# Schematic-ver1.net
KiCad netlist of a schematic drawn in Altium Designer
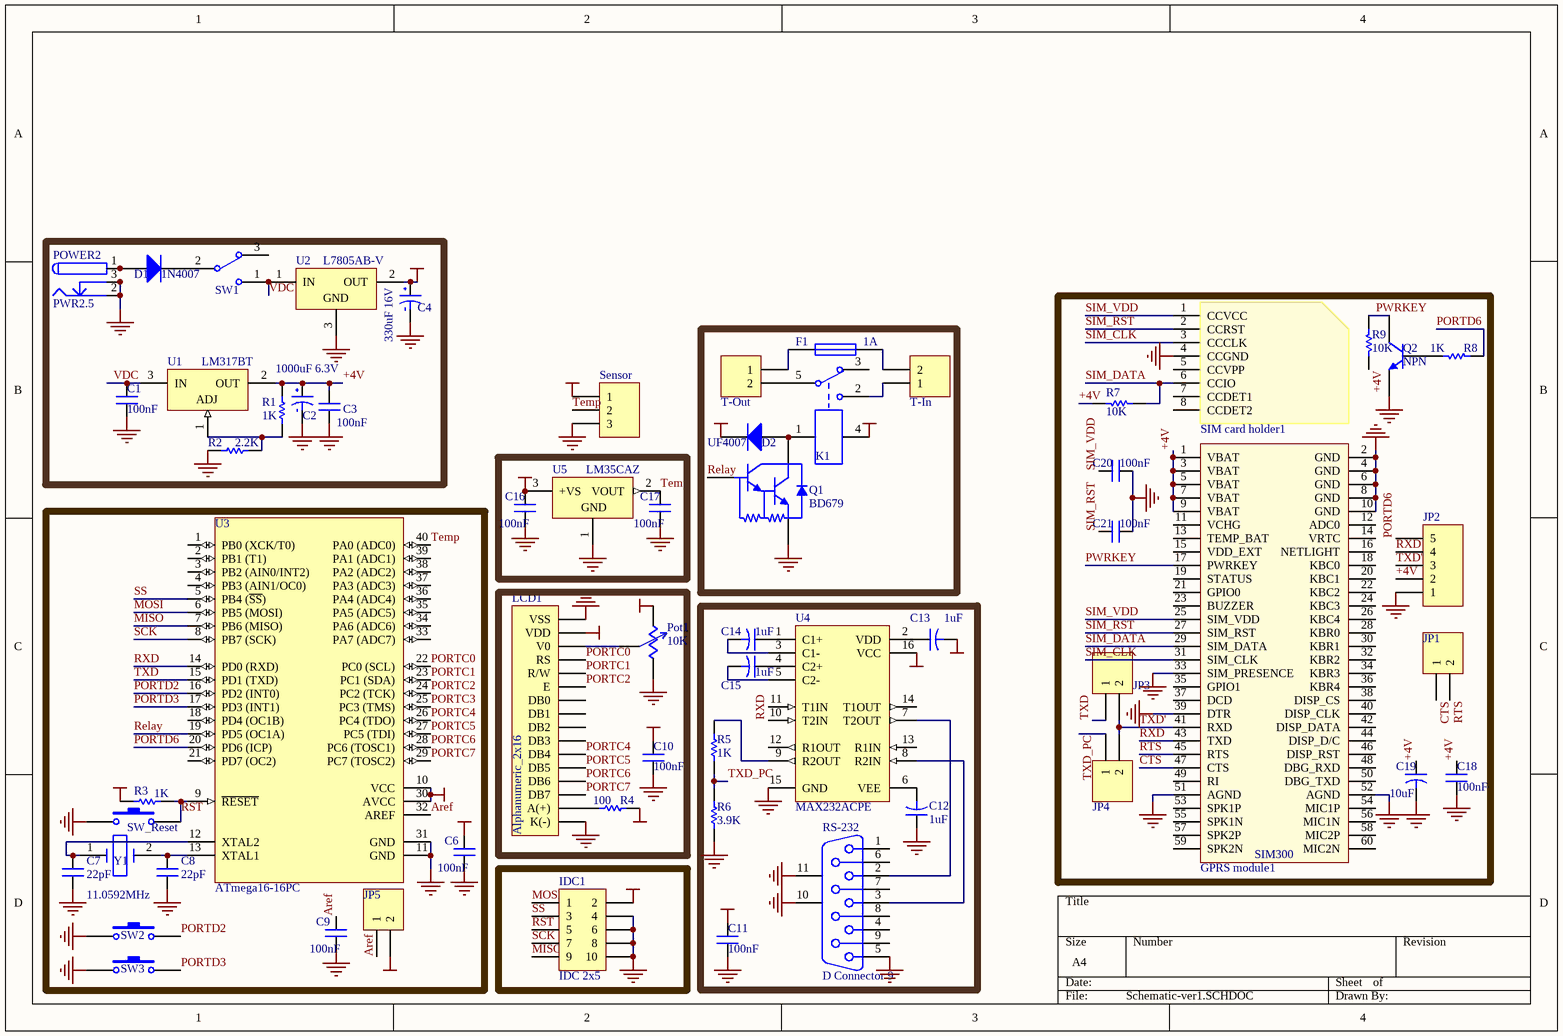
[diagram p0: Schematic-ver1.SCHDOC]

(export (version "E")
  (design (tool "Eeschema 10.0.6"))
  (components
    (comp (ref "C1")
      (value "Cap_Ceramic")
      (footprint "Cap_Ceramic")
      (fields (field (name "ALTIUM_UNNAMED_1") "100nF"))
      (libsource (lib "MMTcomponnents") (part "Cap_Ceramic"))
    )
    (comp (ref "C2")
      (value "Cap_5mm")
      (footprint "Cap_5mm")
      (fields (field (name "ALTIUM_UNNAMED_1") "1000uF 6.3V"))
      (libsource (lib "MMTcomponnents") (part "Cap_5mm"))
    )
    (comp (ref "C3")
      (value "Cap_Ceramic")
      (footprint "Cap_Ceramic")
      (fields (field (name "ALTIUM_UNNAMED_1") "100nF"))
      (libsource (lib "MMTcomponnents") (part "Cap_Ceramic"))
    )
    (comp (ref "C4")
      (value "Cap_4mm")
      (footprint "Cap_4mm")
      (fields (field (name "ALTIUM_UNNAMED_1") "330uF 16V"))
      (libsource (lib "MMTcomponnents") (part "Cap_4mm"))
    )
    (comp (ref "C6")
      (value "Cap_Tantalium")
      (footprint "Cap_Ceramic")
      (fields (field (name "ALTIUM_UNNAMED_1") "100nF"))
      (libsource (lib "MMTcomponnents") (part "Cap_Ceramic"))
    )
    (comp (ref "C7")
      (value "Cap_Ceramic")
      (footprint "Cap_Ceramic")
      (fields (field (name "ALTIUM_UNNAMED_1") "22pF"))
      (libsource (lib "MMTcomponnents") (part "Cap_Ceramic"))
    )
    (comp (ref "C8")
      (value "Cap_Ceramic")
      (footprint "Cap_Ceramic")
      (fields (field (name "ALTIUM_UNNAMED_1") "22pF"))
      (libsource (lib "MMTcomponnents") (part "Cap_Ceramic"))
    )
    (comp (ref "C9")
      (value "Cap_Tantalium")
      (footprint "Cap_Ceramic")
      (fields (field (name "ALTIUM_UNNAMED_1") "100nF"))
      (libsource (lib "MMTcomponnents") (part "Cap_Ceramic"))
    )
    (comp (ref "C10")
      (value "Cap_Tantalium")
      (footprint "Cap_Ceramic")
      (fields (field (name "ALTIUM_UNNAMED_1") "100nF"))
      (libsource (lib "MMTcomponnents") (part "Cap_Ceramic"))
    )
    (comp (ref "C11")
      (value "Cap_Tantalium")
      (footprint "Cap_Ceramic")
      (fields (field (name "ALTIUM_UNNAMED_1") "100nF"))
      (libsource (lib "MMTcomponnents") (part "Cap_Ceramic"))
    )
    (comp (ref "C12")
      (value "Cap_Small")
      (footprint "Cap_Small")
      (fields (field (name "ALTIUM_UNNAMED_1") "1uF"))
      (libsource (lib "MMTcomponnents") (part "Cap_Small"))
    )
    (comp (ref "C13")
      (value "Cap_Small")
      (footprint "Cap_Small")
      (fields (field (name "ALTIUM_UNNAMED_1") "1uF"))
      (libsource (lib "MMTcomponnents") (part "Cap_Small"))
    )
    (comp (ref "C14")
      (value "Cap_Small")
      (footprint "Cap_Small")
      (fields (field (name "ALTIUM_UNNAMED_1") "1uF"))
      (libsource (lib "MMTcomponnents") (part "Cap_Small"))
    )
    (comp (ref "C15")
      (value "Cap_Small")
      (footprint "Cap_Small")
      (fields (field (name "ALTIUM_UNNAMED_1") "1uF"))
      (libsource (lib "MMTcomponnents") (part "Cap_Small"))
    )
    (comp (ref "C16")
      (value "Cap_Tantalium")
      (footprint "Cap_Ceramic")
      (fields (field (name "ALTIUM_UNNAMED_1") "100nF"))
      (libsource (lib "MMTcomponnents") (part "Cap_Ceramic"))
    )
    (comp (ref "C17")
      (value "Cap_Tantalium")
      (footprint "Cap_Ceramic")
      (fields (field (name "ALTIUM_UNNAMED_1") "100nF"))
      (libsource (lib "MMTcomponnents") (part "Cap_Ceramic"))
    )
    (comp (ref "C18")
      (value "Cap_Tantalium")
      (footprint "Cap_Ceramic")
      (fields (field (name "ALTIUM_UNNAMED_1") "100nF"))
      (libsource (lib "MMTcomponnents") (part "Cap_Ceramic"))
    )
    (comp (ref "C19")
      (value "Cap_Small")
      (footprint "Cap_Small")
      (fields (field (name "ALTIUM_UNNAMED_1") "10uF"))
      (libsource (lib "MMTcomponnents") (part "Cap_Small"))
    )
    (comp (ref "C20")
      (value "Cap_Tantalium")
      (footprint "Cap_Ceramic")
      (fields (field (name "ALTIUM_UNNAMED_1") "100nF"))
      (libsource (lib "MMTcomponnents") (part "Cap_Ceramic"))
    )
    (comp (ref "C21")
      (value "Cap_Tantalium")
      (footprint "Cap_Ceramic")
      (fields (field (name "ALTIUM_UNNAMED_1") "100nF"))
      (libsource (lib "MMTcomponnents") (part "Cap_Ceramic"))
    )
    (comp (ref "D1")
      (value "1N4007")
      (footprint "Diode 1N4001")
      (libsource (lib "MMTcomponnents") (part "Diode 1N4001"))
    )
    (comp (ref "D2")
      (value "UF4007")
      (footprint "Diode 1N4001")
      (libsource (lib "MMTcomponnents") (part "Diode 1N4001"))
    )
    (comp (ref "F1")
      (value "Fuse2")
      (footprint "Fuse2")
      (fields (field (name "ALTIUM_UNNAMED_1") "1A"))
      (libsource (lib "MMTcomponnents") (part "Fuse2"))
    )
    (comp (ref "GPRS module1")
      (value "SIM300")
      (footprint "SIM300")
      (libsource (lib "MMTcomponnents") (part "SIM300"))
    )
    (comp (ref "IDC1")
      (value "IDC 2x5")
      (footprint "IDC 2x5")
      (libsource (lib "MMTcomponnents") (part "IDC 2x5"))
    )
    (comp (ref "JP1")
      (value "Header 2")
      (footprint "HDR1X2")
      (description "Header, 2-Pin")
      (fields (field (name "PUBLISHER") "Altium Limited"))
      (libsource (lib "Miscellaneous Connectors") (part "Header 2"))
    )
    (comp (ref "JP2")
      (value "Header 5H")
      (footprint "HDR1X5H")
      (description "Header, 5-Pin, Right Angle")
      (fields (field (name "PUBLISHER") "Altium Limited"))
      (libsource (lib "Miscellaneous Connectors") (part "Header 5H"))
    )
    (comp (ref "JP3")
      (value "Header 2")
      (footprint "HDR1X2")
      (description "Header, 2-Pin")
      (fields (field (name "PUBLISHER") "Altium Limited"))
      (libsource (lib "Miscellaneous Connectors") (part "Header 2"))
    )
    (comp (ref "JP4")
      (value "Header 2")
      (footprint "HDR1X2")
      (description "Header, 2-Pin")
      (fields (field (name "PUBLISHER") "Altium Limited"))
      (libsource (lib "") (part "Header 2_1"))
    )
    (comp (ref "JP5")
      (value "Header 2")
      (footprint "HDR1X2")
      (description "Header, 2-Pin")
      (fields (field (name "PUBLISHER") "Altium Limited"))
      (libsource (lib "Miscellaneous Connectors") (part "Header 2"))
    )
    (comp (ref "K1")
      (value "Relay")
      (footprint "Relay_2")
      (libsource (lib "MMTcomponnents") (part "Relay_2"))
    )
    (comp (ref "LCD1")
      (value "Alphanumeric_2x16")
      (footprint "LCD_Alphanumeric_2x16")
      (libsource (lib "MMTcomponnents") (part "LCD_Alphanumeric_2x16"))
    )
    (comp (ref "Pot1")
      (value "Rpot")
      (footprint "POT1")
      (fields (field (name "ALTIUM_UNNAMED_1") "10K"))
      (libsource (lib "MMTcomponnents") (part "POT1"))
    )
    (comp (ref "POWER2")
      (value "PWR2.5")
      (footprint "KLD-0202")
      (description "Low Voltage Power Supply Connector")
      (fields (field (name "PUBLISHER") "Altium Limited"))
      (libsource (lib "Miscellaneous Connectors") (part "PWR2.5"))
    )
    (comp (ref "Q1") (value "BD679") (footprint "BD679") (libsource (lib "MMTcomponnents") (part "BD679")))
    (comp (ref "Q2")
      (value "NPN")
      (footprint "BCY-W3")
      (description "NPN Bipolar Transistor")
      (fields (field (name "PUBLISHER") "Altium Limited"))
      (libsource (lib "Miscellaneous Devices") (part "NPN"))
    )
    (comp (ref "R1")
      (value "1K")
      (footprint "AXIAL-0.3")
      (description "Resistor")
      (fields (field (name "Comment") "Res1") (field (name "PUBLISHER") "Altium Limited"))
      (libsource (lib "Miscellaneous Devices") (part "Res1"))
    )
    (comp (ref "R2")
      (value "2.2K")
      (footprint "AXIAL-0.3")
      (description "Resistor")
      (fields (field (name "Comment") "Res1") (field (name "PUBLISHER") "Altium Limited"))
      (libsource (lib "Miscellaneous Devices") (part "Res1"))
    )
    (comp (ref "R3")
      (value "1K")
      (footprint "AXIAL-0.3")
      (description "Resistor")
      (fields (field (name "Comment") "Res1") (field (name "PUBLISHER") "Altium Limited"))
      (libsource (lib "Miscellaneous Devices") (part "Res1"))
    )
    (comp (ref "R4")
      (value "100")
      (footprint "AXIAL-0.3")
      (description "Resistor")
      (fields (field (name "Comment") "Res1") (field (name "PUBLISHER") "Altium Limited"))
      (libsource (lib "Miscellaneous Devices") (part "Res1"))
    )
    (comp (ref "R5")
      (value "1K")
      (footprint "AXIAL-0.3")
      (description "Resistor")
      (fields (field (name "Comment") "Res1") (field (name "PUBLISHER") "Altium Limited"))
      (libsource (lib "Miscellaneous Devices") (part "Res1"))
    )
    (comp (ref "R6")
      (value "3.9K")
      (footprint "AXIAL-0.3")
      (description "Resistor")
      (fields (field (name "Comment") "Res1") (field (name "PUBLISHER") "Altium Limited"))
      (libsource (lib "Miscellaneous Devices") (part "Res1"))
    )
    (comp (ref "R7")
      (value "10K")
      (footprint "AXIAL-0.3")
      (description "Resistor")
      (fields (field (name "Comment") "Res1") (field (name "PUBLISHER") "Altium Limited"))
      (libsource (lib "Miscellaneous Devices") (part "Res1"))
    )
    (comp (ref "R8")
      (value "1K")
      (footprint "AXIAL-0.3")
      (description "Resistor")
      (fields (field (name "Comment") "Res1") (field (name "PUBLISHER") "Altium Limited"))
      (libsource (lib "Miscellaneous Devices") (part "Res1"))
    )
    (comp (ref "R9")
      (value "10K")
      (footprint "AXIAL-0.3")
      (description "Resistor")
      (fields (field (name "Comment") "Res1") (field (name "PUBLISHER") "Altium Limited"))
      (libsource (lib "") (part "Res1_1"))
    )
    (comp (ref "RS-232")
      (value "D Connector 9")
      (footprint "DSUB1.385-2H9")
      (description "Receptacle Assembly, 9 Position, Right Angle")
      (fields (field (name "PUBLISHER") "Altium Limited"))
      (libsource (lib "Miscellaneous Connectors") (part "D Connector 9"))
    )
    (comp (ref "Sensor")
      (value "Header 3H")
      (footprint "HDR1X3H")
      (description "Header, 3-Pin, Right Angle")
      (fields (field (name "PUBLISHER") "Altium Limited"))
      (libsource (lib "Miscellaneous Connectors") (part "Header 3H"))
    )
    (comp (ref "SIM card holder1")
      (value "SIM card holder")
      (footprint "SIM card holder")
      (libsource (lib "MMTcomponnents") (part "SIM card holder"))
    )
    (comp (ref "SW1")
      (value "SW_hammer_3")
      (footprint "SW_hammer_3")
      (libsource (lib "MMTcomponnents") (part "SW_hammer_3"))
    )
    (comp (ref "SW2")
      (value "PushButton_small")
      (footprint "PushButton_small")
      (libsource (lib "") (part "PushButton_small_1"))
    )
    (comp (ref "SW3")
      (value "PushButton_small")
      (footprint "PushButton_small")
      (libsource (lib "") (part "PushButton_small_1"))
    )
    (comp (ref "SW_Reset")
      (value "PushButton_small")
      (footprint "PushButton_small")
      (libsource (lib "MMTcomponnents") (part "PushButton_small"))
    )
    (comp (ref "T-In") (value "Phonix") (footprint "Phonix-2") (libsource (lib "") (part "Phonix-2_1")))
    (comp (ref "T-Out")
      (value "Phonix")
      (footprint "Phonix-2")
      (libsource (lib "MMTcomponnents") (part "Phonix-2"))
    )
    (comp (ref "U1")
      (value "LM317BT")
      (footprint "221A-06")
      (description "Three-Terminal Adjustable Output Positive Voltage Regulator")
      (fields (field (name "PUBLISHER") "Altium Limited"))
      (libsource (lib "ON Semi Power Mgt Voltage Regulator") (part "LM317BT"))
    )
    (comp (ref "U2")
      (value "L7805AB-V")
      (footprint "TO220ABN")
      (description "Precision 1A Regulator")
      (fields (field (name "PUBLISHER") "Altium Limited"))
      (libsource (lib "ST Power Mgt Voltage Regulator") (part "L7805AB-V"))
    )
    (comp (ref "U3")
      (value "ATmega16-16PC")
      (footprint "40P6")
      (description "8-Bit AVR Microcontroller with 16K Bytes of In-System Programmable Flash Memory")
      (fields (field (name "PUBLISHER") "Altium Limited"))
      (libsource (lib "Atmel Microcontroller 8-Bit AVR") (part "ATmega16-16PC"))
    )
    (comp (ref "U4")
      (value "MAX232ACPE")
      (footprint "PE16A")
      (description "+5V Powered, Multi-Channel RS-232 Driver/Receiver")
      (fields (field (name "PUBLISHER") "Altium Limited"))
      (libsource (lib "Maxim Communication Transceiver") (part "MAX232ACPE"))
    )
    (comp (ref "U5")
      (value "LM35CAZ")
      (footprint "Z03A")
      (description "Precision CentigradeTemperature Sensor")
      (fields (field (name "PUBLISHER") "Altium Limited"))
      (libsource (lib "NSC Sensor Temperature Sensor") (part "LM35CAZ"))
    )
    (comp (ref "Y1")
      (value "Xtal")
      (footprint "Xtal 1")
      (fields (field (name "ALTIUM_UNNAMED_1") "11.0592MHz"))
      (libsource (lib "MMTcomponnents") (part "Xtal 1"))
    )
  )
  (nets
    (net (code "1") (name "/+4V") (class "Default")
      (node (ref "C18") (pin "2") (pinfunction "2_2") (pintype "passive"))
      (node (ref "C19") (pin "2") (pinfunction "2_2") (pintype "passive"))
      (node (ref "C2") (pin "2") (pinfunction "2_2") (pintype "passive"))
      (node (ref "C3") (pin "2") (pinfunction "2_2") (pintype "passive"))
      (node (ref "GPRS module1") (pin "1") (pinfunction "VBAT_1") (pintype "passive"))
      (node (ref "GPRS module1") (pin "3") (pinfunction "VBAT_3") (pintype "passive"))
      (node (ref "GPRS module1") (pin "5") (pinfunction "VBAT_5") (pintype "passive"))
      (node (ref "GPRS module1") (pin "7") (pinfunction "VBAT_7") (pintype "passive"))
      (node (ref "GPRS module1") (pin "9") (pinfunction "VBAT_9") (pintype "passive"))
      (node (ref "JP2") (pin "2") (pinfunction "2_2") (pintype "passive"))
      (node (ref "R1") (pin "1") (pinfunction "1_1") (pintype "passive"))
      (node (ref "R7") (pin "1") (pinfunction "1_1") (pintype "passive"))
      (node (ref "R9") (pin "2") (pinfunction "2_2") (pintype "passive"))
      (node (ref "U1") (pin "2") (pinfunction "OUT_2") (pintype "power_in"))
    )
    (net (code "2") (name "/Aref") (class "Default")
      (node (ref "C9") (pin "2") (pinfunction "2_2") (pintype "passive"))
      (node (ref "JP5") (pin "1") (pinfunction "1_1") (pintype "passive"))
      (node (ref "U3") (pin "32") (pinfunction "AREF_32") (pintype "passive"))
    )
    (net (code "3") (name "/CTS") (class "Default")
      (node (ref "GPRS module1") (pin "47") (pinfunction "CTS_47") (pintype "passive"))
      (node (ref "JP1") (pin "1") (pinfunction "1_1") (pintype "passive"))
    )
    (net (code "4") (name "/MISO") (class "Default")
      (node (ref "IDC1") (pin "9") (pinfunction "9_9") (pintype "passive"))
      (node (ref "U3") (pin "7") (pinfunction "PB6_(MISO)_7") (pintype "bidirectional"))
    )
    (net (code "5") (name "/MOSI") (class "Default")
      (node (ref "IDC1") (pin "1") (pinfunction "1_1") (pintype "passive"))
      (node (ref "U3") (pin "6") (pinfunction "PB5_(MOSI)_6") (pintype "bidirectional"))
    )
    (net (code "6") (name "/PORTC0") (class "Default")
      (node (ref "LCD1") (pin "4") (pinfunction "RS_4") (pintype "passive"))
      (node (ref "U3") (pin "22") (pinfunction "PC0_(SCL)_22") (pintype "bidirectional"))
    )
    (net (code "7") (name "/PORTC1") (class "Default")
      (node (ref "LCD1") (pin "5") (pinfunction "R/W_5") (pintype "passive"))
      (node (ref "U3") (pin "23") (pinfunction "PC1_(SDA)_23") (pintype "bidirectional"))
    )
    (net (code "8") (name "/PORTC2") (class "Default")
      (node (ref "LCD1") (pin "6") (pinfunction "E_6") (pintype "passive"))
      (node (ref "U3") (pin "24") (pinfunction "PC2_(TCK)_24") (pintype "bidirectional"))
    )
    (net (code "9") (name "/PORTC3") (class "Default")
      (node (ref "U3") (pin "25") (pinfunction "PC3_(TMS)_25") (pintype "bidirectional"))
    )
    (net (code "10") (name "/PORTC4") (class "Default")
      (node (ref "LCD1") (pin "11") (pinfunction "DB4_11") (pintype "passive"))
      (node (ref "U3") (pin "26") (pinfunction "PC4_(TDO)_26") (pintype "bidirectional"))
    )
    (net (code "11") (name "/PORTC5") (class "Default")
      (node (ref "LCD1") (pin "12") (pinfunction "DB5_12") (pintype "passive"))
      (node (ref "U3") (pin "27") (pinfunction "PC5_(TDI)_27") (pintype "bidirectional"))
    )
    (net (code "12") (name "/PORTC6") (class "Default")
      (node (ref "LCD1") (pin "13") (pinfunction "DB6_13") (pintype "passive"))
      (node (ref "U3") (pin "28") (pinfunction "PC6_(TOSC1)_28") (pintype "bidirectional"))
    )
    (net (code "13") (name "/PORTC7") (class "Default")
      (node (ref "LCD1") (pin "14") (pinfunction "DB7_14") (pintype "passive"))
      (node (ref "U3") (pin "29") (pinfunction "PC7_(TOSC2)_29") (pintype "bidirectional"))
    )
    (net (code "14") (name "/PORTD2") (class "Default")
      (node (ref "SW2") (pin "2") (pinfunction "2_2") (pintype "passive"))
      (node (ref "U3") (pin "16") (pinfunction "PD2_(INT0)_16") (pintype "bidirectional"))
    )
    (net (code "15") (name "/PORTD3") (class "Default")
      (node (ref "SW3") (pin "2") (pinfunction "2_2") (pintype "passive"))
      (node (ref "U3") (pin "17") (pinfunction "PD3_(INT1)_17") (pintype "bidirectional"))
    )
    (net (code "16") (name "/PORTD6") (class "Default")
      (node (ref "JP2") (pin "5") (pinfunction "5_5") (pintype "passive"))
      (node (ref "R8") (pin "1") (pinfunction "1_1") (pintype "passive"))
      (node (ref "U3") (pin "20") (pinfunction "PD6_(ICP)_20") (pintype "bidirectional"))
    )
    (net (code "17") (name "/PWRKEY") (class "Default")
      (node (ref "GPRS module1") (pin "17") (pinfunction "PWRKEY_17") (pintype "passive"))
      (node (ref "Q2") (pin "1") (pinfunction "C_1") (pintype "passive"))
      (node (ref "R9") (pin "1") (pinfunction "1_1") (pintype "passive"))
    )
    (net (code "18") (name "/RST") (class "Default")
      (node (ref "IDC1") (pin "5") (pinfunction "5_5") (pintype "passive"))
      (node (ref "R3") (pin "2") (pinfunction "2_2") (pintype "passive"))
      (node (ref "SW_Reset") (pin "1") (pinfunction "1_1") (pintype "passive"))
      (node (ref "U3") (pin "9") (pinfunction "~{RESET}_9") (pintype "input"))
    )
    (net (code "19") (name "/RTS") (class "Default")
      (node (ref "GPRS module1") (pin "45") (pinfunction "RTS_45") (pintype "passive"))
      (node (ref "JP1") (pin "2") (pinfunction "2_2") (pintype "passive"))
    )
    (net (code "20") (name "/RXD") (class "Default")
      (node (ref "GPRS module1") (pin "43") (pinfunction "TXD_43") (pintype "passive"))
      (node (ref "JP2") (pin "4") (pinfunction "4_4") (pintype "passive"))
      (node (ref "U3") (pin "14") (pinfunction "PD0_(RXD)_14") (pintype "bidirectional"))
      (node (ref "U4") (pin "10") (pinfunction "T2IN_10") (pintype "input"))
    )
    (net (code "21") (name "/Relay") (class "Default")
      (node (ref "Q1") (pin "1") (pinfunction "B_1") (pintype "passive"))
      (node (ref "U3") (pin "19") (pinfunction "PD5_(OC1A)_19") (pintype "bidirectional"))
    )
    (net (code "22") (name "/SCK") (class "Default")
      (node (ref "IDC1") (pin "7") (pinfunction "7_7") (pintype "passive"))
      (node (ref "U3") (pin "8") (pinfunction "PB7_(SCK)_8") (pintype "bidirectional"))
    )
    (net (code "23") (name "/SIM_CLK") (class "Default")
      (node (ref "GPRS module1") (pin "31") (pinfunction "SIM_CLK_31") (pintype "passive"))
      (node (ref "SIM card holder1") (pin "3") (pinfunction "CCCLK_3") (pintype "passive"))
    )
    (net (code "24") (name "/SIM_DATA") (class "Default")
      (node (ref "GPRS module1") (pin "29") (pinfunction "SIM_DATA_29") (pintype "passive"))
      (node (ref "R7") (pin "2") (pinfunction "2_2") (pintype "passive"))
      (node (ref "SIM card holder1") (pin "6") (pinfunction "CCIO_6") (pintype "passive"))
    )
    (net (code "25") (name "/SIM_RST") (class "Default")
      (node (ref "C21") (pin "2") (pinfunction "2_2") (pintype "passive"))
      (node (ref "GPRS module1") (pin "27") (pinfunction "SIM_RST_27") (pintype "passive"))
      (node (ref "SIM card holder1") (pin "2") (pinfunction "CCRST_2") (pintype "passive"))
    )
    (net (code "26") (name "/SIM_VDD") (class "Default")
      (node (ref "C20") (pin "2") (pinfunction "2_2") (pintype "passive"))
      (node (ref "GPRS module1") (pin "25") (pinfunction "SIM_VDD_25") (pintype "passive"))
      (node (ref "SIM card holder1") (pin "1") (pinfunction "CCVCC_1") (pintype "passive"))
    )
    (net (code "27") (name "/SS") (class "Default")
      (node (ref "IDC1") (pin "3") (pinfunction "3_3") (pintype "passive"))
      (node (ref "U3") (pin "5") (pinfunction "PB4_(~{SS})_5") (pintype "bidirectional"))
    )
    (net (code "28") (name "/TXD") (class "Default")
      (node (ref "JP3") (pin "1") (pinfunction "1_1") (pintype "passive"))
      (node (ref "U3") (pin "15") (pinfunction "PD1_(TXD)_15") (pintype "bidirectional"))
    )
    (net (code "29") (name "/TXD'") (class "Default")
      (node (ref "GPRS module1") (pin "41") (pinfunction "RXD_41") (pintype "passive"))
      (node (ref "JP2") (pin "3") (pinfunction "3_3") (pintype "passive"))
      (node (ref "JP3") (pin "2") (pinfunction "2_2") (pintype "passive"))
      (node (ref "JP4") (pin "2") (pinfunction "2_2") (pintype "passive"))
    )
    (net (code "30") (name "/TXD_PC") (class "Default")
      (node (ref "JP4") (pin "1") (pinfunction "1_1") (pintype "passive"))
      (node (ref "R5") (pin "1") (pinfunction "1_1") (pintype "passive"))
      (node (ref "R6") (pin "2") (pinfunction "2_2") (pintype "passive"))
    )
    (net (code "31") (name "/Temp") (class "Default")
      (node (ref "C17") (pin "2") (pinfunction "2_2") (pintype "passive"))
      (node (ref "Sensor") (pin "2") (pinfunction "2_2") (pintype "passive"))
      (node (ref "U3") (pin "40") (pinfunction "PA0_(ADC0)_40") (pintype "bidirectional"))
      (node (ref "U5") (pin "2") (pinfunction "VOUT_2") (pintype "output"))
    )
    (net (code "32") (name "/VDC") (class "Default")
      (node (ref "C1") (pin "2") (pinfunction "2_2") (pintype "passive"))
      (node (ref "SW1") (pin "1") (pintype "passive"))
      (node (ref "U1") (pin "3") (pinfunction "IN_3") (pintype "power_in"))
      (node (ref "U2") (pin "1") (pinfunction "IN_1") (pintype "power_in"))
    )
    (net (code "33") (name "GND") (class "Default")
      (node (ref "C1") (pin "1") (pinfunction "1_1") (pintype "passive"))
      (node (ref "C10") (pin "1") (pinfunction "1_1") (pintype "passive"))
      (node (ref "C11") (pin "1") (pinfunction "1_1") (pintype "passive"))
      (node (ref "C12") (pin "2") (pinfunction "2_2") (pintype "passive"))
      (node (ref "C16") (pin "1") (pinfunction "1_1") (pintype "passive"))
      (node (ref "C17") (pin "1") (pinfunction "1_1") (pintype "passive"))
      (node (ref "C18") (pin "1") (pinfunction "1_1") (pintype "passive"))
      (node (ref "C19") (pin "1") (pinfunction "1_1") (pintype "passive"))
      (node (ref "C2") (pin "1") (pinfunction "1_1") (pintype "passive"))
      (node (ref "C20") (pin "1") (pinfunction "1_1") (pintype "passive"))
      (node (ref "C21") (pin "1") (pinfunction "1_1") (pintype "passive"))
      (node (ref "C3") (pin "1") (pinfunction "1_1") (pintype "passive"))
      (node (ref "C4") (pin "1") (pinfunction "1_1") (pintype "passive"))
      (node (ref "C6") (pin "1") (pinfunction "1_1") (pintype "passive"))
      (node (ref "C7") (pin "1") (pinfunction "1_1") (pintype "passive"))
      (node (ref "C8") (pin "1") (pinfunction "1_1") (pintype "passive"))
      (node (ref "C9") (pin "1") (pinfunction "1_1") (pintype "passive"))
      (node (ref "GPRS module1") (pin "10") (pinfunction "GND_10") (pintype "passive"))
      (node (ref "GPRS module1") (pin "2") (pinfunction "GND_2") (pintype "passive"))
      (node (ref "GPRS module1") (pin "33") (pinfunction "SIM_PRESENCE_33") (pintype "passive"))
      (node (ref "GPRS module1") (pin "39") (pinfunction "DTR_39") (pintype "passive"))
      (node (ref "GPRS module1") (pin "4") (pinfunction "GND_4") (pintype "passive"))
      (node (ref "GPRS module1") (pin "51") (pinfunction "AGND_51") (pintype "passive"))
      (node (ref "GPRS module1") (pin "52") (pinfunction "AGND_52") (pintype "passive"))
      (node (ref "GPRS module1") (pin "6") (pinfunction "GND_6") (pintype "passive"))
      (node (ref "GPRS module1") (pin "8") (pinfunction "GND_8") (pintype "passive"))
      (node (ref "IDC1") (pin "10") (pinfunction "10_10") (pintype "passive"))
      (node (ref "IDC1") (pin "4") (pinfunction "4_4") (pintype "passive"))
      (node (ref "IDC1") (pin "6") (pinfunction "6_6") (pintype "passive"))
      (node (ref "IDC1") (pin "8") (pinfunction "8_8") (pintype "passive"))
      (node (ref "JP2") (pin "1") (pinfunction "1_1") (pintype "passive"))
      (node (ref "LCD1") (pin "1") (pinfunction "VSS_1") (pintype "passive"))
      (node (ref "LCD1") (pin "16") (pinfunction "K(-)_16") (pintype "passive"))
      (node (ref "POWER2") (pin "2") (pintype "power_in"))
      (node (ref "POWER2") (pin "2A") (pintype "power_in"))
      (node (ref "POWER2") (pin "2B") (pintype "power_in"))
      (node (ref "POWER2") (pin "3") (pintype "power_in"))
      (node (ref "POWER2") (pin "3A") (pintype "power_in"))
      (node (ref "POWER2") (pin "3B") (pintype "power_in"))
      (node (ref "Pot1") (pin "1") (pinfunction "1_1") (pintype "passive"))
      (node (ref "Q1") (pin "3") (pinfunction "E_3") (pintype "passive"))
      (node (ref "Q2") (pin "3") (pinfunction "E_3") (pintype "passive"))
      (node (ref "R2") (pin "1") (pinfunction "1_1") (pintype "passive"))
      (node (ref "R6") (pin "1") (pinfunction "1_1") (pintype "passive"))
      (node (ref "RS-232") (pin "10") (pinfunction "MH1_10") (pintype "passive"))
      (node (ref "RS-232") (pin "11") (pinfunction "MH2_11") (pintype "passive"))
      (node (ref "RS-232") (pin "5") (pinfunction "5_5") (pintype "passive"))
      (node (ref "SIM card holder1") (pin "4") (pinfunction "CCGND_4") (pintype "passive"))
      (node (ref "SW2") (pin "1") (pinfunction "1_1") (pintype "passive"))
      (node (ref "SW3") (pin "1") (pinfunction "1_1") (pintype "passive"))
      (node (ref "SW_Reset") (pin "2") (pinfunction "2_2") (pintype "passive"))
      (node (ref "Sensor") (pin "3") (pinfunction "3_3") (pintype "passive"))
      (node (ref "U2") (pin "3") (pinfunction "GND_3") (pintype "power_in"))
      (node (ref "U3") (pin "11") (pinfunction "GND_11") (pintype "power_in"))
      (node (ref "U3") (pin "31") (pinfunction "GND_31") (pintype "power_in"))
      (node (ref "U4") (pin "15") (pinfunction "GND_15") (pintype "power_in"))
      (node (ref "U5") (pin "1") (pinfunction "GND_1") (pintype "power_in"))
    )
    (net (code "34") (name "Net-(D1-PadA)") (class "Default")
      (node (ref "D1") (pin "A") (pinfunction "A_A") (pintype "passive"))
      (node (ref "POWER2") (pin "1") (pintype "power_in"))
      (node (ref "POWER2") (pin "1A") (pintype "power_in"))
      (node (ref "POWER2") (pin "1B") (pintype "power_in"))
    )
    (net (code "35") (name "Net-(D1-PadK)") (class "Default")
      (node (ref "D1") (pin "K") (pinfunction "K_K") (pintype "passive"))
      (node (ref "SW1") (pin "2") (pintype "passive"))
    )
    (net (code "36") (name "Net-(F1-Pad1)") (class "Default")
      (node (ref "F1") (pin "1") (pinfunction "1_1") (pintype "passive"))
      (node (ref "T-In") (pin "2") (pinfunction "2_2") (pintype "passive"))
    )
    (net (code "37") (name "Net-(F1-Pad2)") (class "Default")
      (node (ref "F1") (pin "2") (pinfunction "2_2") (pintype "passive"))
      (node (ref "T-Out") (pin "1") (pinfunction "1_1") (pintype "passive"))
    )
    (net (code "38") (name "Net-(K1-Pad2)") (class "Default")
      (node (ref "K1") (pin "2") (pinfunction "2_2") (pintype "passive"))
      (node (ref "T-In") (pin "1") (pinfunction "1_1") (pintype "passive"))
    )
    (net (code "39") (name "Net-(K1-Pad5)") (class "Default")
      (node (ref "K1") (pin "5") (pinfunction "5_5") (pintype "passive"))
      (node (ref "T-Out") (pin "2") (pinfunction "2_2") (pintype "passive"))
    )
    (net (code "40") (name "Net-(LCD1-A(+))") (class "Default")
      (node (ref "LCD1") (pin "15") (pinfunction "A(+)_15") (pintype "passive"))
      (node (ref "R4") (pin "1") (pinfunction "1_1") (pintype "passive"))
    )
    (net (code "41") (name "Net-(LCD1-V0)") (class "Default")
      (node (ref "LCD1") (pin "3") (pinfunction "V0_3") (pintype "passive"))
      (node (ref "Pot1") (pin "3") (pinfunction "3_3") (pintype "passive"))
    )
    (net (code "42") (name "Net-(Q1-C)") (class "Default")
      (node (ref "D2") (pin "A") (pinfunction "A_A") (pintype "passive"))
      (node (ref "K1") (pin "1") (pinfunction "1_1") (pintype "passive"))
      (node (ref "Q1") (pin "2") (pinfunction "C_2") (pintype "passive"))
    )
    (net (code "43") (name "Net-(Q2-B)") (class "Default")
      (node (ref "Q2") (pin "2") (pinfunction "B_2") (pintype "passive"))
      (node (ref "R8") (pin "2") (pinfunction "2_2") (pintype "passive"))
    )
    (net (code "44") (name "Net-(U1-ADJ)") (class "Default")
      (node (ref "R1") (pin "2") (pinfunction "2_2") (pintype "passive"))
      (node (ref "R2") (pin "2") (pinfunction "2_2") (pintype "passive"))
      (node (ref "U1") (pin "1") (pinfunction "ADJ_1") (pintype "input"))
    )
    (net (code "45") (name "Net-(U3-XTAL1)") (class "Default")
      (node (ref "C8") (pin "2") (pinfunction "2_2") (pintype "passive"))
      (node (ref "U3") (pin "13") (pinfunction "XTAL1_13") (pintype "passive"))
      (node (ref "Y1") (pin "2") (pinfunction "2_2") (pintype "passive"))
    )
    (net (code "46") (name "Net-(U3-XTAL2)") (class "Default")
      (node (ref "C7") (pin "2") (pinfunction "2_2") (pintype "passive"))
      (node (ref "U3") (pin "12") (pinfunction "XTAL2_12") (pintype "passive"))
      (node (ref "Y1") (pin "1") (pinfunction "1_1") (pintype "passive"))
    )
    (net (code "47") (name "Net-(U4-C1+)") (class "Default")
      (node (ref "C14") (pin "2") (pinfunction "2_2") (pintype "passive"))
      (node (ref "U4") (pin "1") (pinfunction "C1+_1") (pintype "passive"))
    )
    (net (code "48") (name "Net-(U4-C1-)") (class "Default")
      (node (ref "C14") (pin "1") (pinfunction "1_1") (pintype "passive"))
      (node (ref "U4") (pin "3") (pinfunction "C1-_3") (pintype "passive"))
    )
    (net (code "49") (name "Net-(U4-C2+)") (class "Default")
      (node (ref "C15") (pin "2") (pinfunction "2_2") (pintype "passive"))
      (node (ref "U4") (pin "4") (pinfunction "C2+_4") (pintype "passive"))
    )
    (net (code "50") (name "Net-(U4-C2-)") (class "Default")
      (node (ref "C15") (pin "1") (pinfunction "1_1") (pintype "passive"))
      (node (ref "U4") (pin "5") (pinfunction "C2-_5") (pintype "passive"))
    )
    (net (code "51") (name "Net-(U4-R2IN)") (class "Default")
      (node (ref "RS-232") (pin "3") (pinfunction "3_3") (pintype "passive"))
      (node (ref "U4") (pin "8") (pinfunction "R2IN_8") (pintype "input"))
    )
    (net (code "52") (name "Net-(U4-R2OUT)") (class "Default")
      (node (ref "R5") (pin "2") (pinfunction "2_2") (pintype "passive"))
      (node (ref "U4") (pin "9") (pinfunction "R2OUT_9") (pintype "output"))
    )
    (net (code "53") (name "Net-(U4-T2OUT)") (class "Default")
      (node (ref "RS-232") (pin "2") (pinfunction "2_2") (pintype "passive"))
      (node (ref "U4") (pin "7") (pinfunction "T2OUT_7") (pintype "output"))
    )
    (net (code "54") (name "Net-(U4-VDD)") (class "Default")
      (node (ref "C13") (pin "2") (pinfunction "2_2") (pintype "passive"))
      (node (ref "U4") (pin "2") (pinfunction "VDD_2") (pintype "power_in"))
    )
    (net (code "55") (name "Net-(U4-VEE)") (class "Default")
      (node (ref "C12") (pin "1") (pinfunction "1_1") (pintype "passive"))
      (node (ref "U4") (pin "6") (pinfunction "VEE_6") (pintype "power_in"))
    )
    (net (code "56") (name "VCC") (class "Default")
      (node (ref "C10") (pin "2") (pinfunction "2_2") (pintype "passive"))
      (node (ref "C11") (pin "2") (pinfunction "2_2") (pintype "passive"))
      (node (ref "C13") (pin "1") (pinfunction "1_1") (pintype "passive"))
      (node (ref "C16") (pin "2") (pinfunction "2_2") (pintype "passive"))
      (node (ref "C4") (pin "2") (pinfunction "2_2") (pintype "passive"))
      (node (ref "C6") (pin "2") (pinfunction "2_2") (pintype "passive"))
      (node (ref "D2") (pin "K") (pinfunction "K_K") (pintype "passive"))
      (node (ref "IDC1") (pin "2") (pinfunction "2_2") (pintype "passive"))
      (node (ref "JP5") (pin "2") (pinfunction "2_2") (pintype "passive"))
      (node (ref "K1") (pin "4") (pinfunction "4_4") (pintype "passive"))
      (node (ref "LCD1") (pin "2") (pinfunction "VDD_2") (pintype "passive"))
      (node (ref "Pot1") (pin "2") (pinfunction "2_2") (pintype "passive"))
      (node (ref "R3") (pin "1") (pinfunction "1_1") (pintype "passive"))
      (node (ref "R4") (pin "2") (pinfunction "2_2") (pintype "passive"))
      (node (ref "Sensor") (pin "1") (pinfunction "1_1") (pintype "passive"))
      (node (ref "U2") (pin "2") (pinfunction "OUT_2") (pintype "power_in"))
      (node (ref "U3") (pin "10") (pinfunction "VCC_10") (pintype "power_in"))
      (node (ref "U3") (pin "30") (pinfunction "AVCC_30") (pintype "power_in"))
      (node (ref "U4") (pin "16") (pinfunction "VCC_16") (pintype "power_in"))
      (node (ref "U5") (pin "3") (pinfunction "+VS_3") (pintype "power_in"))
    )
    (net (code "57") (name "unconnected-(GPRS module1-ADC0-Pad12)") (class "Default")
      (node (ref "GPRS module1") (pin "12") (pinfunction "ADC0_12") (pintype "passive"))
    )
    (net (code "58") (name "unconnected-(GPRS module1-BUZZER-Pad23)") (class "Default")
      (node (ref "GPRS module1") (pin "23") (pinfunction "BUZZER_23") (pintype "passive"))
    )
    (net (code "59") (name "unconnected-(GPRS module1-DBG_RXD-Pad48)") (class "Default")
      (node (ref "GPRS module1") (pin "48") (pinfunction "DBG_RXD_48") (pintype "passive"))
    )
    (net (code "60") (name "unconnected-(GPRS module1-DBG_TXD-Pad50)") (class "Default")
      (node (ref "GPRS module1") (pin "50") (pinfunction "DBG_TXD_50") (pintype "passive"))
    )
    (net (code "61") (name "unconnected-(GPRS module1-DCD-Pad37)") (class "Default")
      (node (ref "GPRS module1") (pin "37") (pinfunction "DCD_37") (pintype "passive"))
    )
    (net (code "62") (name "unconnected-(GPRS module1-DISP_CLK-Pad40)") (class "Default")
      (node (ref "GPRS module1") (pin "40") (pinfunction "DISP_CLK_40") (pintype "passive"))
    )
    (net (code "63") (name "unconnected-(GPRS module1-DISP_CS-Pad38)") (class "Default")
      (node (ref "GPRS module1") (pin "38") (pinfunction "DISP_CS_38") (pintype "passive"))
    )
    (net (code "64") (name "unconnected-(GPRS module1-DISP_DATA-Pad42)") (class "Default")
      (node (ref "GPRS module1") (pin "42") (pinfunction "DISP_DATA_42") (pintype "passive"))
    )
    (net (code "65") (name "unconnected-(GPRS module1-DISP_D{slash}C-Pad44)") (class "Default")
      (node (ref "GPRS module1") (pin "44") (pinfunction "DISP_D/C_44") (pintype "passive"))
    )
    (net (code "66") (name "unconnected-(GPRS module1-DISP_RST-Pad46)") (class "Default")
      (node (ref "GPRS module1") (pin "46") (pinfunction "DISP_RST_46") (pintype "passive"))
    )
    (net (code "67") (name "unconnected-(GPRS module1-GPIO0-Pad21)") (class "Default")
      (node (ref "GPRS module1") (pin "21") (pinfunction "GPIO0_21") (pintype "passive"))
    )
    (net (code "68") (name "unconnected-(GPRS module1-GPIO1-Pad35)") (class "Default")
      (node (ref "GPRS module1") (pin "35") (pinfunction "GPIO1_35") (pintype "passive"))
    )
    (net (code "69") (name "unconnected-(GPRS module1-KBC0-Pad18)") (class "Default")
      (node (ref "GPRS module1") (pin "18") (pinfunction "KBC0_18") (pintype "passive"))
    )
    (net (code "70") (name "unconnected-(GPRS module1-KBC1-Pad20)") (class "Default")
      (node (ref "GPRS module1") (pin "20") (pinfunction "KBC1_20") (pintype "passive"))
    )
    (net (code "71") (name "unconnected-(GPRS module1-KBC2-Pad22)") (class "Default")
      (node (ref "GPRS module1") (pin "22") (pinfunction "KBC2_22") (pintype "passive"))
    )
    (net (code "72") (name "unconnected-(GPRS module1-KBC3-Pad24)") (class "Default")
      (node (ref "GPRS module1") (pin "24") (pinfunction "KBC3_24") (pintype "passive"))
    )
    (net (code "73") (name "unconnected-(GPRS module1-KBC4-Pad26)") (class "Default")
      (node (ref "GPRS module1") (pin "26") (pinfunction "KBC4_26") (pintype "passive"))
    )
    (net (code "74") (name "unconnected-(GPRS module1-KBR0-Pad28)") (class "Default")
      (node (ref "GPRS module1") (pin "28") (pinfunction "KBR0_28") (pintype "passive"))
    )
    (net (code "75") (name "unconnected-(GPRS module1-KBR1-Pad30)") (class "Default")
      (node (ref "GPRS module1") (pin "30") (pinfunction "KBR1_30") (pintype "passive"))
    )
    (net (code "76") (name "unconnected-(GPRS module1-KBR2-Pad32)") (class "Default")
      (node (ref "GPRS module1") (pin "32") (pinfunction "KBR2_32") (pintype "passive"))
    )
    (net (code "77") (name "unconnected-(GPRS module1-KBR3-Pad34)") (class "Default")
      (node (ref "GPRS module1") (pin "34") (pinfunction "KBR3_34") (pintype "passive"))
    )
    (net (code "78") (name "unconnected-(GPRS module1-KBR4-Pad36)") (class "Default")
      (node (ref "GPRS module1") (pin "36") (pinfunction "KBR4_36") (pintype "passive"))
    )
    (net (code "79") (name "unconnected-(GPRS module1-MIC1N-Pad56)") (class "Default")
      (node (ref "GPRS module1") (pin "56") (pinfunction "MIC1N_56") (pintype "passive"))
    )
    (net (code "80") (name "unconnected-(GPRS module1-MIC1P-Pad54)") (class "Default")
      (node (ref "GPRS module1") (pin "54") (pinfunction "MIC1P_54") (pintype "passive"))
    )
    (net (code "81") (name "unconnected-(GPRS module1-MIC2N-Pad60)") (class "Default")
      (node (ref "GPRS module1") (pin "60") (pinfunction "MIC2N_60") (pintype "passive"))
    )
    (net (code "82") (name "unconnected-(GPRS module1-MIC2P-Pad58)") (class "Default")
      (node (ref "GPRS module1") (pin "58") (pinfunction "MIC2P_58") (pintype "passive"))
    )
    (net (code "83") (name "unconnected-(GPRS module1-NETLIGHT-Pad16)") (class "Default")
      (node (ref "GPRS module1") (pin "16") (pinfunction "NETLIGHT_16") (pintype "passive"))
    )
    (net (code "84") (name "unconnected-(GPRS module1-RI-Pad49)") (class "Default")
      (node (ref "GPRS module1") (pin "49") (pinfunction "RI_49") (pintype "passive"))
    )
    (net (code "85") (name "unconnected-(GPRS module1-SPK1N-Pad55)") (class "Default")
      (node (ref "GPRS module1") (pin "55") (pinfunction "SPK1N_55") (pintype "passive"))
    )
    (net (code "86") (name "unconnected-(GPRS module1-SPK1P-Pad53)") (class "Default")
      (node (ref "GPRS module1") (pin "53") (pinfunction "SPK1P_53") (pintype "passive"))
    )
    (net (code "87") (name "unconnected-(GPRS module1-SPK2N-Pad59)") (class "Default")
      (node (ref "GPRS module1") (pin "59") (pinfunction "SPK2N_59") (pintype "passive"))
    )
    (net (code "88") (name "unconnected-(GPRS module1-SPK2P-Pad57)") (class "Default")
      (node (ref "GPRS module1") (pin "57") (pinfunction "SPK2P_57") (pintype "passive"))
    )
    (net (code "89") (name "unconnected-(GPRS module1-STATUS-Pad19)") (class "Default")
      (node (ref "GPRS module1") (pin "19") (pinfunction "STATUS_19") (pintype "passive"))
    )
    (net (code "90") (name "unconnected-(GPRS module1-TEMP_BAT-Pad13)") (class "Default")
      (node (ref "GPRS module1") (pin "13") (pinfunction "TEMP_BAT_13") (pintype "passive"))
    )
    (net (code "91") (name "unconnected-(GPRS module1-VCHG-Pad11)") (class "Default")
      (node (ref "GPRS module1") (pin "11") (pinfunction "VCHG_11") (pintype "passive"))
    )
    (net (code "92") (name "unconnected-(GPRS module1-VDD_EXT-Pad15)") (class "Default")
      (node (ref "GPRS module1") (pin "15") (pinfunction "VDD_EXT_15") (pintype "passive"))
    )
    (net (code "93") (name "unconnected-(GPRS module1-VRTC-Pad14)") (class "Default")
      (node (ref "GPRS module1") (pin "14") (pinfunction "VRTC_14") (pintype "passive"))
    )
    (net (code "94") (name "unconnected-(K1-Pad3)") (class "Default")
      (node (ref "K1") (pin "3") (pinfunction "3_3") (pintype "passive"))
    )
    (net (code "95") (name "unconnected-(LCD1-DB0-Pad7)") (class "Default")
      (node (ref "LCD1") (pin "7") (pinfunction "DB0_7") (pintype "passive"))
    )
    (net (code "96") (name "unconnected-(LCD1-DB1-Pad8)") (class "Default")
      (node (ref "LCD1") (pin "8") (pinfunction "DB1_8") (pintype "passive"))
    )
    (net (code "97") (name "unconnected-(LCD1-DB2-Pad9)") (class "Default")
      (node (ref "LCD1") (pin "9") (pinfunction "DB2_9") (pintype "passive"))
    )
    (net (code "98") (name "unconnected-(LCD1-DB3-Pad10)") (class "Default")
      (node (ref "LCD1") (pin "10") (pinfunction "DB3_10") (pintype "passive"))
    )
    (net (code "99") (name "unconnected-(RS-232-Pad1)") (class "Default")
      (node (ref "RS-232") (pin "1") (pinfunction "1_1") (pintype "passive"))
    )
    (net (code "100") (name "unconnected-(RS-232-Pad4)") (class "Default")
      (node (ref "RS-232") (pin "4") (pinfunction "4_4") (pintype "passive"))
    )
    (net (code "101") (name "unconnected-(RS-232-Pad6)") (class "Default")
      (node (ref "RS-232") (pin "6") (pinfunction "6_6") (pintype "passive"))
    )
    (net (code "102") (name "unconnected-(RS-232-Pad7)") (class "Default")
      (node (ref "RS-232") (pin "7") (pinfunction "7_7") (pintype "passive"))
    )
    (net (code "103") (name "unconnected-(RS-232-Pad8)") (class "Default")
      (node (ref "RS-232") (pin "8") (pinfunction "8_8") (pintype "passive"))
    )
    (net (code "104") (name "unconnected-(RS-232-Pad9)") (class "Default")
      (node (ref "RS-232") (pin "9") (pinfunction "9_9") (pintype "passive"))
    )
    (net (code "105") (name "unconnected-(SIM card holder1-CCDET1-Pad7)") (class "Default")
      (node (ref "SIM card holder1") (pin "7") (pinfunction "CCDET1_7") (pintype "passive"))
    )
    (net (code "106") (name "unconnected-(SIM card holder1-CCDET2-Pad8)") (class "Default")
      (node (ref "SIM card holder1") (pin "8") (pinfunction "CCDET2_8") (pintype "passive"))
    )
    (net (code "107") (name "unconnected-(SIM card holder1-CCVPP-Pad5)") (class "Default")
      (node (ref "SIM card holder1") (pin "5") (pinfunction "CCVPP_5") (pintype "passive"))
    )
    (net (code "108") (name "unconnected-(SW1-Pad3)") (class "Default")
      (node (ref "SW1") (pin "3") (pintype "passive"))
    )
    (net (code "109") (name "unconnected-(U3-PA1_(ADC1)-Pad39)") (class "Default")
      (node (ref "U3") (pin "39") (pinfunction "PA1_(ADC1)_39") (pintype "bidirectional"))
    )
    (net (code "110") (name "unconnected-(U3-PA2_(ADC2)-Pad38)") (class "Default")
      (node (ref "U3") (pin "38") (pinfunction "PA2_(ADC2)_38") (pintype "bidirectional"))
    )
    (net (code "111") (name "unconnected-(U3-PA3_(ADC3)-Pad37)") (class "Default")
      (node (ref "U3") (pin "37") (pinfunction "PA3_(ADC3)_37") (pintype "bidirectional"))
    )
    (net (code "112") (name "unconnected-(U3-PA4_(ADC4)-Pad36)") (class "Default")
      (node (ref "U3") (pin "36") (pinfunction "PA4_(ADC4)_36") (pintype "bidirectional"))
    )
    (net (code "113") (name "unconnected-(U3-PA5_(ADC5)-Pad35)") (class "Default")
      (node (ref "U3") (pin "35") (pinfunction "PA5_(ADC5)_35") (pintype "bidirectional"))
    )
    (net (code "114") (name "unconnected-(U3-PA6_(ADC6)-Pad34)") (class "Default")
      (node (ref "U3") (pin "34") (pinfunction "PA6_(ADC6)_34") (pintype "bidirectional"))
    )
    (net (code "115") (name "unconnected-(U3-PA7_(ADC7)-Pad33)") (class "Default")
      (node (ref "U3") (pin "33") (pinfunction "PA7_(ADC7)_33") (pintype "bidirectional"))
    )
    (net (code "116") (name "unconnected-(U3-PB0_(XCK{slash}T0)-Pad1)") (class "Default")
      (node (ref "U3") (pin "1") (pinfunction "PB0_(XCK/T0)_1") (pintype "bidirectional"))
    )
    (net (code "117") (name "unconnected-(U3-PB1_(T1)-Pad2)") (class "Default")
      (node (ref "U3") (pin "2") (pinfunction "PB1_(T1)_2") (pintype "bidirectional"))
    )
    (net (code "118") (name "unconnected-(U3-PB2_(AIN0{slash}INT2)-Pad3)") (class "Default")
      (node (ref "U3") (pin "3") (pinfunction "PB2_(AIN0/INT2)_3") (pintype "bidirectional"))
    )
    (net (code "119") (name "unconnected-(U3-PB3_(AIN1{slash}OC0)-Pad4)") (class "Default")
      (node (ref "U3") (pin "4") (pinfunction "PB3_(AIN1/OC0)_4") (pintype "bidirectional"))
    )
    (net (code "120") (name "unconnected-(U3-PD4_(OC1B)-Pad18)") (class "Default")
      (node (ref "U3") (pin "18") (pinfunction "PD4_(OC1B)_18") (pintype "bidirectional"))
    )
    (net (code "121") (name "unconnected-(U3-PD7_(OC2)-Pad21)") (class "Default")
      (node (ref "U3") (pin "21") (pinfunction "PD7_(OC2)_21") (pintype "bidirectional"))
    )
    (net (code "122") (name "unconnected-(U4-R1IN-Pad13)") (class "Default")
      (node (ref "U4") (pin "13") (pinfunction "R1IN_13") (pintype "input"))
    )
    (net (code "123") (name "unconnected-(U4-R1OUT-Pad12)") (class "Default")
      (node (ref "U4") (pin "12") (pinfunction "R1OUT_12") (pintype "output"))
    )
    (net (code "124") (name "unconnected-(U4-T1IN-Pad11)") (class "Default")
      (node (ref "U4") (pin "11") (pinfunction "T1IN_11") (pintype "input"))
    )
    (net (code "125") (name "unconnected-(U4-T1OUT-Pad14)") (class "Default")
      (node (ref "U4") (pin "14") (pinfunction "T1OUT_14") (pintype "output"))
    )
  )
)
